# Synch_Demod.net
KiCad netlist of a schematic drawn in Altium Designer
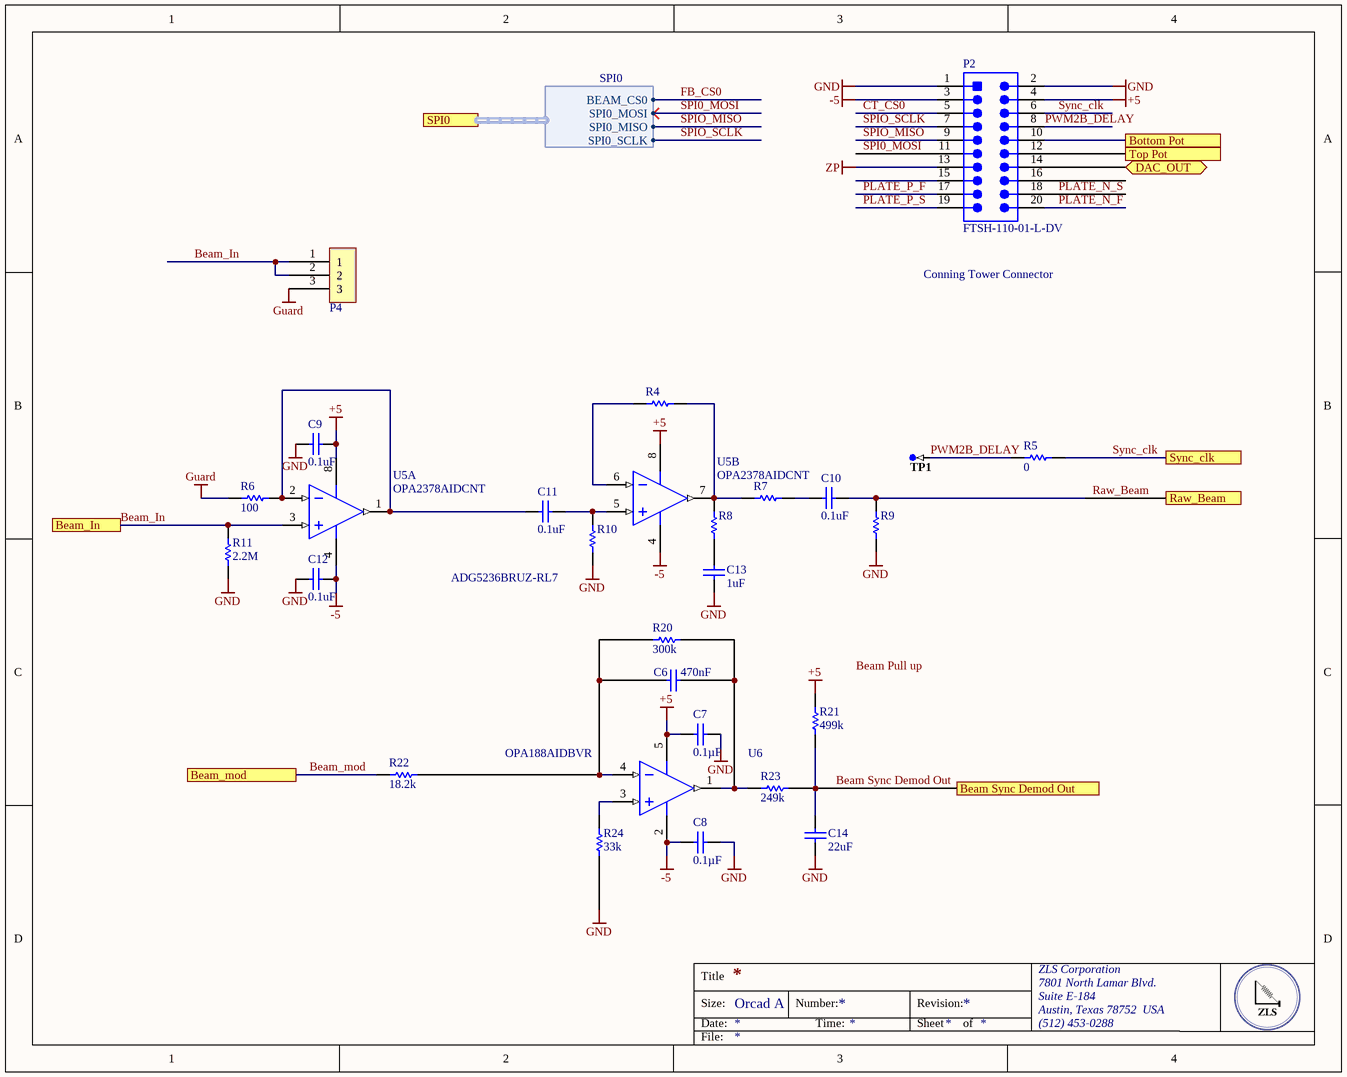
[diagram p0: Synch_Demod.SchDoc]

(export (version "E")
  (design (tool "Eeschema 10.0.6"))
  (components
    (comp (ref "C6")
      (value "470nF")
      (footprint "CAPC0805(2012)75_L")
      (description "CAP CER 0.47UF 25V X7R 0805")
      (fields
        (field (name "MANUFACTURER") "Murata Electronics North America")
        (field (name "MANUFACTURER PART NUMBER") "GRM219R71E474KA88D")
      )
      (libsource (lib "Altium Content Vault") (part "CMP-1036-02117-1"))
    )
    (comp (ref "C7")
      (value "CAP CER 0.1UF 25V X7R 0805")
      (footprint "CAPC0805(2012)145_N")
      (fields
        (field (name "MANUFACTURER") "Murata Electronics North America")
        (field (name "MANUFACTURER PART NUMBER") "GRM21BR71E104KA01L")
        (field (name "CAPACITANCE") "0.1µF")
        (field (name "TOLERANCE") "±10%")
      )
      (libsource (lib "Altium Content Vault") (part "CMP-1036-04795-1"))
    )
    (comp (ref "C8")
      (value "CAP CER 0.1UF 25V X7R 0805")
      (footprint "CAPC0805(2012)145_N")
      (fields
        (field (name "MANUFACTURER") "Murata Electronics North America")
        (field (name "MANUFACTURER PART NUMBER") "GRM21BR71E104KA01L")
        (field (name "CAPACITANCE") "0.1µF")
        (field (name "TOLERANCE") "±10%")
      )
      (libsource (lib "Altium Content Vault") (part "CMP-1036-04795-1"))
    )
    (comp (ref "C9")
      (value "0.1uF")
      (footprint "CAPC0402(1005)60_L")
      (description "CAP CER 0.1UF 10V X7R 0402")
      (fields
        (field (name "MANUFACTURER") "Murata Electronics North America")
        (field (name "MANUFACTURER PART NUMBER") "GRM155R71A104KA01D")
      )
      (libsource (lib "Altium Content Vault") (part "CMP-1034-00252-1"))
    )
    (comp (ref "C10")
      (value "0.1uF")
      (footprint "CAPC0402(1005)60_L")
      (description "CAP CER 0.1UF 10V X7R 0402")
      (fields
        (field (name "MANUFACTURER") "Murata Electronics North America")
        (field (name "MANUFACTURER PART NUMBER") "GRM155R71A104KA01D")
      )
      (libsource (lib "Altium Content Vault") (part "CMP-1034-00252-1"))
    )
    (comp (ref "C11")
      (value "0.1uF")
      (footprint "CAPC0402(1005)60_L")
      (description "CAP CER 0.1UF 10V X7R 0402")
      (fields
        (field (name "MANUFACTURER") "Murata Electronics North America")
        (field (name "MANUFACTURER PART NUMBER") "GRM155R71A104KA01D")
      )
      (libsource (lib "Altium Content Vault") (part "CMP-1034-00252-1"))
    )
    (comp (ref "C12")
      (value "0.1uF")
      (footprint "CAPC0402(1005)60_L")
      (description "CAP CER 0.1UF 10V X7R 0402")
      (fields
        (field (name "MANUFACTURER") "Murata Electronics North America")
        (field (name "MANUFACTURER PART NUMBER") "GRM155R71A104KA01D")
      )
      (libsource (lib "Altium Content Vault") (part "CMP-1034-00252-1"))
    )
    (comp (ref "C13")
      (value "1uF")
      (footprint "CAPC0402(1005)60_L")
      (description "CAP CER 0.1UF 10V X7R 0402")
      (fields
        (field (name "MANUFACTURER") "Murata Electronics North America")
        (field (name "MANUFACTURER PART NUMBER") "GRM155R71A104KA01D")
      )
      (libsource (lib "Altium Content Vault") (part "CMP-1034-00252-1"))
    )
    (comp (ref "C14")
      (value "22uF")
      (footprint "CAPC0805(2012)75_L")
      (description "CAP CER 22UF 25V X5R 0805")
      (fields
        (field (name "MANUFACTURER") "Murata Electronics North America")
        (field (name "MANUFACTURER PART NUMBER") "GRM21BR61E226ME44L")
      )
      (libsource (lib "Altium Content Vault") (part "CMP-1036-02117-1"))
    )
    (comp (ref "P2")
      (value "FTSH-110-01-L-DV")
      (footprint "SMTC-FTSH-110-01-L-DV_V")
      (description "Male Header, Pitch 1.27 mm, 2 x 10 Position, Height 6.1 mm, -55 to 125 degC, RoHS, Tube")
      (fields (field (name "MANUFACTURER") "Samtec"))
      (libsource (lib "Altium Content Vault") (part "CN-2P-M-R20_V1"))
    )
    (comp (ref "P4")
      (value "Triax_Conn")
      (footprint "Triax_Conn")
      (libsource (lib "ZLS_Schematic_lib") (part "Triax_Conn"))
    )
    (comp (ref "R4")
      (value "~")
      (footprint "RESC0402(1005)_M")
      (libsource (lib "Altium Content Vault") (part "CMP-1011-00463-1"))
    )
    (comp (ref "R5")
      (value "0")
      (footprint "RESC0402(1005)_M")
      (libsource (lib "Altium Content Vault") (part "CMP-1011-00463-1"))
    )
    (comp (ref "R6")
      (value "100")
      (footprint "RESC0402(1005)_M")
      (libsource (lib "Altium Content Vault") (part "CMP-1011-00463-1"))
    )
    (comp (ref "R7")
      (value "~")
      (footprint "RESC0402(1005)_M")
      (libsource (lib "Altium Content Vault") (part "CMP-1011-00463-1"))
    )
    (comp (ref "R8")
      (value "~")
      (footprint "RESC0402(1005)_M")
      (libsource (lib "Altium Content Vault") (part "CMP-1011-00463-1"))
    )
    (comp (ref "R9")
      (value "~")
      (footprint "RESC0402(1005)_M")
      (libsource (lib "Altium Content Vault") (part "CMP-1011-00463-1"))
    )
    (comp (ref "R10")
      (value "~")
      (footprint "RESC0402(1005)_M")
      (libsource (lib "Altium Content Vault") (part "CMP-1011-00463-1"))
    )
    (comp (ref "R11")
      (value "2.2M")
      (footprint "RESC0402(1005)_M")
      (libsource (lib "Altium Content Vault") (part "CMP-1011-00463-1"))
    )
    (comp (ref "R20")
      (value "300k")
      (footprint "RESC0402(1005)_M")
      (libsource (lib "Altium Content Vault") (part "CMP-1011-00463-1"))
    )
    (comp (ref "R21")
      (value "499k")
      (footprint "RESC0402(1005)_M")
      (libsource (lib "Altium Content Vault") (part "CMP-1011-00463-1"))
    )
    (comp (ref "R22")
      (value "18.2k")
      (footprint "RESC0402(1005)_M")
      (libsource (lib "Altium Content Vault") (part "CMP-1011-00463-1"))
    )
    (comp (ref "R23")
      (value "249k")
      (footprint "RESC0402(1005)_M")
      (libsource (lib "Altium Content Vault") (part "CMP-1011-00463-1"))
    )
    (comp (ref "R24")
      (value "33k")
      (footprint "RESC0402(1005)_M")
      (libsource (lib "Altium Content Vault") (part "CMP-1011-00463-1"))
    )
    (comp (ref "TP1")
      (value "TP-SM-C-100")
      (footprint "TP-SM-C-100")
      (description "Test Point, Surface Mount, Circular, Pad Diameter 1 mm")
      (fields (field (name "MANUFACTURER") "No Vendor"))
      (libsource (lib "Altium Content Vault") (part "CMP-0484-00002-2"))
    )
    (comp (ref "U5")
      (value "OPA2378AIDCNT")
      (footprint "DCN0008A_M")
      (fields (field (name "MANUFACTURER") "Texas Instruments"))
      (libsource (lib "Altium Content Vault") (part "TI-OPA-8_2"))
    )
    (comp (ref "U6")
      (value "OPA188AIDBVR")
      (footprint "DBV0005A_M")
      (fields (field (name "MANUFACTURER") "Texas Instruments"))
      (libsource (lib "Altium Content Vault") (part "CMP-0809-00005-2"))
    )
  )
  (nets
    (net (code "2") (name "+5") (class "Default")
      (node (ref "C7") (pin "1") (pinfunction "1_1") (pintype "passive"))
      (node (ref "C9") (pin "2") (pinfunction "2_2") (pintype "passive"))
      (node (ref "P2") (pin "4") (pinfunction "4_4") (pintype "passive"))
      (node (ref "R21") (pin "1") (pinfunction "1_1") (pintype "passive"))
      (node (ref "U5") (pin "8") (pinfunction "V+_8") (pintype "power_in"))
      (node (ref "U6") (pin "5") (pinfunction "V+_5") (pintype "power_in"))
    )
    (net (code "3") (name "-5") (class "Default")
      (node (ref "C12") (pin "2") (pinfunction "2_2") (pintype "passive"))
      (node (ref "C8") (pin "1") (pinfunction "1_1") (pintype "passive"))
      (node (ref "P2") (pin "3") (pinfunction "3_3") (pintype "passive"))
      (node (ref "U5") (pin "4") (pinfunction "V-_4") (pintype "power_in"))
      (node (ref "U6") (pin "2") (pinfunction "V-_2") (pintype "power_in"))
    )
    (net (code "5") (name "/Beam Sync Demod Out") (class "Default")
      (node (ref "C14") (pin "2") (pinfunction "2_2") (pintype "passive"))
      (node (ref "R21") (pin "2") (pinfunction "2_2") (pintype "passive"))
      (node (ref "R23") (pin "2") (pinfunction "2_2") (pintype "passive"))
    )
    (net (code "6") (name "/Beam_In") (class "Default")
      (node (ref "P4") (pin "1") (pinfunction "1_1") (pintype "passive"))
      (node (ref "P4") (pin "2") (pinfunction "2_2") (pintype "passive"))
      (node (ref "R11") (pin "2") (pinfunction "2_2") (pintype "passive"))
      (node (ref "U5") (pin "3") (pinfunction "IN_A+_3") (pintype "input"))
    )
    (net (code "7") (name "/Beam_mod") (class "Default")
      (node (ref "R22") (pin "1") (pinfunction "1_1") (pintype "passive"))
    )
    (net (code "8") (name "/Bottom Pot") (class "Default")
      (node (ref "P2") (pin "10") (pinfunction "10_10") (pintype "passive"))
    )
    (net (code "9") (name "/CT_CS0") (class "Default")
      (node (ref "P2") (pin "5") (pinfunction "5_5") (pintype "passive"))
    )
    (net (code "10") (name "/DAC_OUT") (class "Default")
      (node (ref "P2") (pin "14") (pinfunction "14_14") (pintype "passive"))
    )
    (net (code "12") (name "/PLATE_N_F") (class "Default")
      (node (ref "P2") (pin "20") (pinfunction "20_20") (pintype "passive"))
    )
    (net (code "13") (name "/PLATE_N_S") (class "Default")
      (node (ref "P2") (pin "18") (pinfunction "18_18") (pintype "passive"))
    )
    (net (code "14") (name "/PLATE_P_F") (class "Default")
      (node (ref "P2") (pin "17") (pinfunction "17_17") (pintype "passive"))
    )
    (net (code "15") (name "/PLATE_P_S") (class "Default")
      (node (ref "P2") (pin "19") (pinfunction "19_19") (pintype "passive"))
    )
    (net (code "16") (name "/PWM2B_DELAY") (class "Default")
      (node (ref "P2") (pin "8") (pinfunction "8_8") (pintype "passive"))
      (node (ref "R5") (pin "1") (pinfunction "1_1") (pintype "passive"))
      (node (ref "TP1") (pin "1") (pinfunction "1_1") (pintype "input"))
    )
    (net (code "17") (name "/Raw_Beam") (class "Default")
      (node (ref "C10") (pin "2") (pinfunction "2_2") (pintype "passive"))
      (node (ref "R9") (pin "1") (pinfunction "1_1") (pintype "passive"))
    )
    (net (code "18") (name "/SPI0_MOSI") (class "Default")
      (node (ref "P2") (pin "11") (pinfunction "11_11") (pintype "passive+no_connect"))
    )
    (net (code "19") (name "/SPIO_MISO") (class "Default")
      (node (ref "P2") (pin "9") (pinfunction "9_9") (pintype "passive"))
    )
    (net (code "20") (name "/SPIO_SCLK") (class "Default")
      (node (ref "P2") (pin "7") (pinfunction "7_7") (pintype "passive"))
    )
    (net (code "21") (name "/Sync_clk") (class "Default")
      (node (ref "P2") (pin "6") (pinfunction "6_6") (pintype "passive"))
      (node (ref "R5") (pin "2") (pinfunction "2_2") (pintype "passive"))
    )
    (net (code "22") (name "/Top Pot") (class "Default")
      (node (ref "P2") (pin "12") (pinfunction "12_12") (pintype "passive"))
    )
    (net (code "24") (name "GND") (class "Default")
      (node (ref "C12") (pin "1") (pinfunction "1_1") (pintype "passive"))
      (node (ref "C13") (pin "1") (pinfunction "1_1") (pintype "passive"))
      (node (ref "C14") (pin "1") (pinfunction "1_1") (pintype "passive"))
      (node (ref "C7") (pin "2") (pinfunction "2_2") (pintype "passive"))
      (node (ref "C8") (pin "2") (pinfunction "2_2") (pintype "passive"))
      (node (ref "C9") (pin "1") (pinfunction "1_1") (pintype "passive"))
      (node (ref "P2") (pin "1") (pinfunction "1_1") (pintype "passive"))
      (node (ref "P2") (pin "2") (pinfunction "2_2") (pintype "passive"))
      (node (ref "R10") (pin "2") (pinfunction "2_2") (pintype "passive"))
      (node (ref "R11") (pin "1") (pinfunction "1_1") (pintype "passive"))
      (node (ref "R24") (pin "2") (pinfunction "2_2") (pintype "passive"))
      (node (ref "R9") (pin "2") (pinfunction "2_2") (pintype "passive"))
    )
    (net (code "25") (name "Guard") (class "Default")
      (node (ref "P4") (pin "3") (pinfunction "3_3") (pintype "passive"))
      (node (ref "R6") (pin "2") (pinfunction "2_2") (pintype "passive"))
    )
    (net (code "26") (name "Net-(C10-Pad1)") (class "Default")
      (node (ref "C10") (pin "1") (pinfunction "1_1") (pintype "passive"))
      (node (ref "R7") (pin "1") (pinfunction "1_1") (pintype "passive"))
    )
    (net (code "27") (name "Net-(C13-Pad2)") (class "Default")
      (node (ref "C13") (pin "2") (pinfunction "2_2") (pintype "passive"))
      (node (ref "R8") (pin "2") (pinfunction "2_2") (pintype "passive"))
    )
    (net (code "28") (name "Net-(U5A-IN_A-)") (class "Default")
      (node (ref "C11") (pin "1") (pinfunction "1_1") (pintype "passive"))
      (node (ref "R6") (pin "1") (pinfunction "1_1") (pintype "passive"))
      (node (ref "U5") (pin "1") (pinfunction "OUT_A_1") (pintype "output"))
      (node (ref "U5") (pin "2") (pinfunction "IN_A-_2") (pintype "input"))
    )
    (net (code "29") (name "Net-(U5B-IN_B+)") (class "Default")
      (node (ref "C11") (pin "2") (pinfunction "2_2") (pintype "passive"))
      (node (ref "R10") (pin "1") (pinfunction "1_1") (pintype "passive"))
      (node (ref "U5") (pin "5") (pinfunction "IN_B+_5") (pintype "input"))
    )
    (net (code "30") (name "Net-(U5B-IN_B-)") (class "Default")
      (node (ref "R4") (pin "2") (pinfunction "2_2") (pintype "passive"))
      (node (ref "U5") (pin "6") (pinfunction "IN_B-_6") (pintype "input"))
    )
    (net (code "31") (name "Net-(U5B-OUT_B)") (class "Default")
      (node (ref "R4") (pin "1") (pinfunction "1_1") (pintype "passive"))
      (node (ref "R7") (pin "2") (pinfunction "2_2") (pintype "passive"))
      (node (ref "R8") (pin "1") (pinfunction "1_1") (pintype "passive"))
      (node (ref "U5") (pin "7") (pinfunction "OUT_B_7") (pintype "output"))
    )
    (net (code "32") (name "Net-(U6-IN+)") (class "Default")
      (node (ref "R24") (pin "1") (pinfunction "1_1") (pintype "passive"))
      (node (ref "U6") (pin "3") (pinfunction "IN+_3") (pintype "input"))
    )
    (net (code "33") (name "Net-(U6-IN-)") (class "Default")
      (node (ref "C6") (pin "1") (pinfunction "1_1") (pintype "passive"))
      (node (ref "R20") (pin "1") (pinfunction "1_1") (pintype "passive"))
      (node (ref "R22") (pin "2") (pinfunction "2_2") (pintype "passive"))
      (node (ref "U6") (pin "4") (pinfunction "IN-_4") (pintype "input"))
    )
    (net (code "34") (name "Net-(U6-OUT)") (class "Default")
      (node (ref "C6") (pin "2") (pinfunction "2_2") (pintype "passive"))
      (node (ref "R20") (pin "2") (pinfunction "2_2") (pintype "passive"))
      (node (ref "R23") (pin "1") (pinfunction "1_1") (pintype "passive"))
      (node (ref "U6") (pin "1") (pinfunction "OUT_1") (pintype "output"))
    )
    (net (code "35") (name "ZP") (class "Default")
      (node (ref "P2") (pin "13") (pinfunction "13_13") (pintype "passive"))
    )
    (net (code "36") (name "unconnected-(P2-Pad15)") (class "Default")
      (node (ref "P2") (pin "15") (pinfunction "15_15") (pintype "passive"))
    )
    (net (code "37") (name "unconnected-(P2-Pad16)") (class "Default")
      (node (ref "P2") (pin "16") (pinfunction "16_16") (pintype "passive"))
    )
  )
)
